# ZigBee_CC2420RTC.net
KiCad netlist of a schematic drawn in Altium Designer
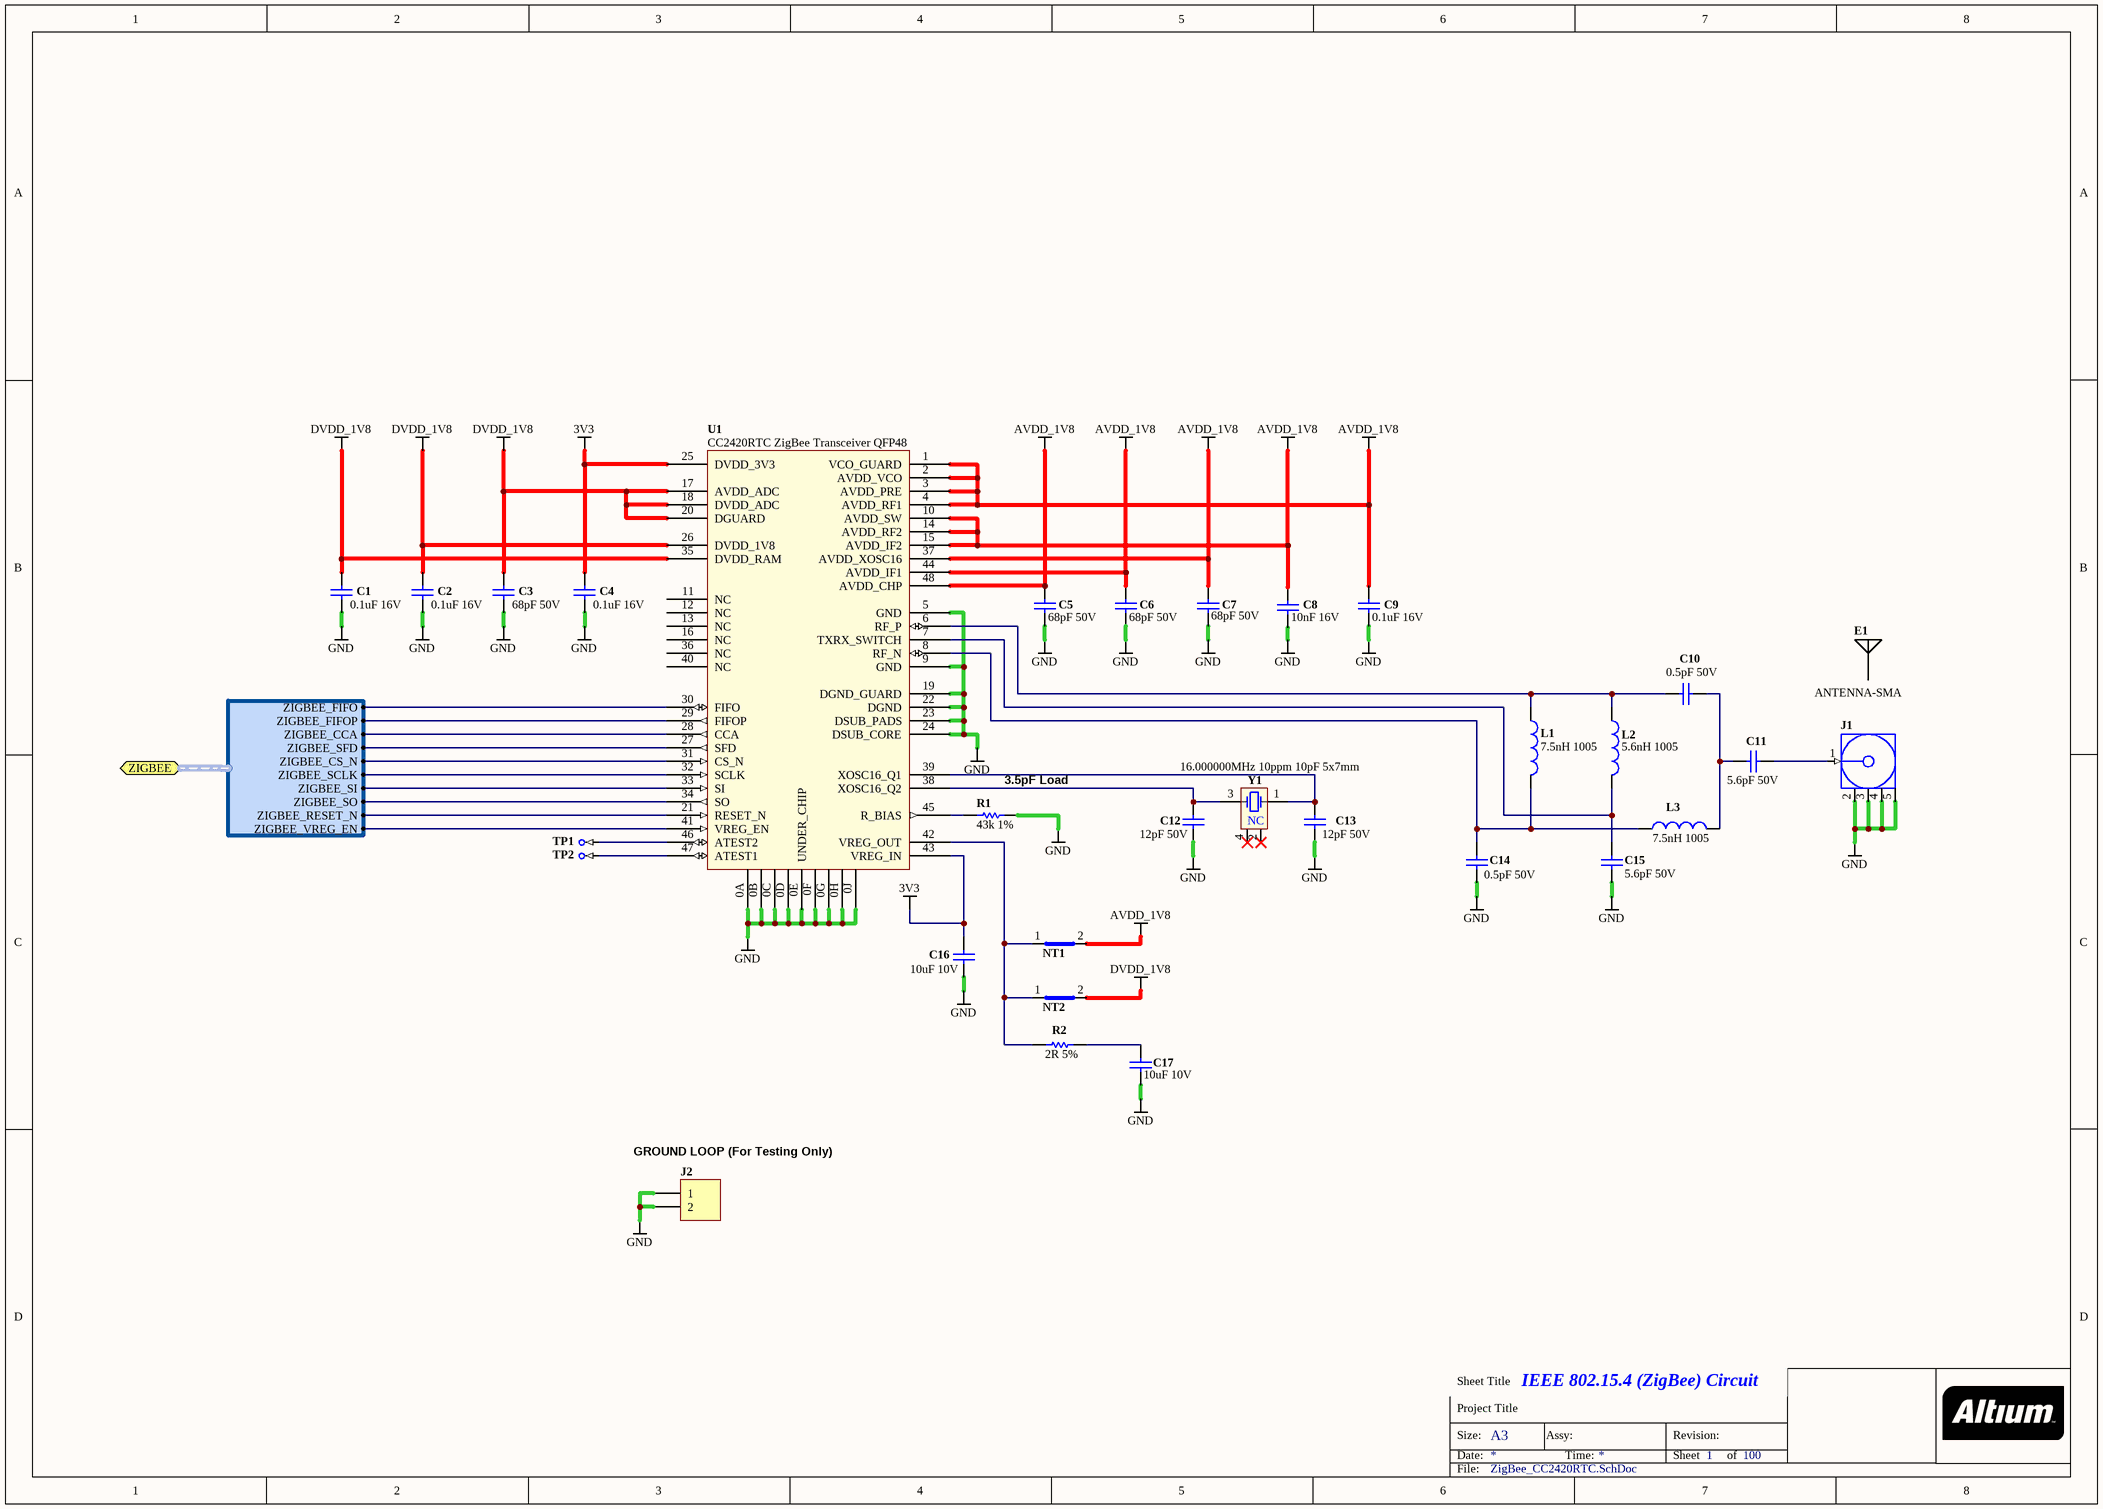
[diagram p0: ZigBee_CC2420RTC.SchDoc]

(export (version "E")
  (design (tool "Eeschema 10.0.6"))
  (components
    (comp (ref "C1")
      (value "0.1uF 16V")
      (footprint "CAPC1005-STAR")
      (description "Capacitor, Ceramic, 0.1uF 10% 16V 0402 (1005) X7R")
      (fields (field (name "TOLERANCE") "10 %"))
      (libsource (lib "AltiumDesignLibrary") (part "CAP-NP"))
    )
    (comp (ref "C2")
      (value "0.1uF 16V")
      (footprint "CAPC1005-STAR")
      (description "Capacitor, Ceramic, 0.1uF 10% 16V 0402 (1005) X7R")
      (fields (field (name "TOLERANCE") "10 %"))
      (libsource (lib "AltiumDesignLibrary") (part "CAP-NP"))
    )
    (comp (ref "C3")
      (value "68pF 50V")
      (footprint "CAPC1005-STAR")
      (description "Capacitor, Ceramic, 68pF 5% 50V 0402 (1005) COG")
      (fields (field (name "TOLERANCE") "5 %"))
      (libsource (lib "AltiumDesignLibrary") (part "CAP-NP"))
    )
    (comp (ref "C4")
      (value "0.1uF 16V")
      (footprint "CAPC1005-STAR")
      (description "Capacitor, Ceramic, 0.1uF 10% 16V 0402 (1005) X7R")
      (fields (field (name "TOLERANCE") "10 %"))
      (libsource (lib "AltiumDesignLibrary") (part "CAP-NP"))
    )
    (comp (ref "C5")
      (value "68pF 50V")
      (footprint "CAPC1005-STAR")
      (description "Capacitor, Ceramic, 68pF 5% 50V 0402 (1005) COG")
      (fields (field (name "TOLERANCE") "5 %"))
      (libsource (lib "AltiumDesignLibrary") (part "CAP-NP"))
    )
    (comp (ref "C6")
      (value "68pF 50V")
      (footprint "CAPC1005-STAR")
      (description "Capacitor, Ceramic, 68pF 5% 50V 0402 (1005) COG")
      (fields (field (name "TOLERANCE") "5 %"))
      (libsource (lib "AltiumDesignLibrary") (part "CAP-NP"))
    )
    (comp (ref "C7")
      (value "68pF 50V")
      (footprint "CAPC1005-STAR")
      (description "Capacitor, Ceramic, 68pF 5% 50V 0402 (1005) COG")
      (fields (field (name "TOLERANCE") "5 %"))
      (libsource (lib "AltiumDesignLibrary") (part "CAP-NP"))
    )
    (comp (ref "C8")
      (value "10nF 16V")
      (footprint "CAPC1005-STAR")
      (description "Capacitor, Ceramic, 10nF 10% 16V 0402 (1005) X7R")
      (fields (field (name "TOLERANCE") "10 %"))
      (libsource (lib "AltiumDesignLibrary") (part "CAP-NP"))
    )
    (comp (ref "C9")
      (value "0.1uF 16V")
      (footprint "CAPC1005-STAR")
      (description "Capacitor, Ceramic, 0.1uF 10% 16V 0402 (1005) X7R")
      (fields (field (name "TOLERANCE") "10 %"))
      (libsource (lib "AltiumDesignLibrary") (part "CAP-NP"))
    )
    (comp (ref "C10")
      (value "0.5pF 50V")
      (footprint "CAPC1005-STAR")
      (description "Capacitor, Ceramic, 0.5pF 50V 0402 (1005) COG")
      (fields (field (name "TOLERANCE") "20 %"))
      (libsource (lib "AltiumDesignLibrary") (part "CAP-NP"))
    )
    (comp (ref "C11")
      (value "5.6pF 50V")
      (footprint "CAPC1005-STAR")
      (description "Capacitor, Ceramic, 5.6pF 5% 50V 0402 (1005) COG")
      (fields (field (name "TOLERANCE") "5 %"))
      (libsource (lib "AltiumDesignLibrary") (part "CAP-NP"))
    )
    (comp (ref "C12")
      (value "12pF 50V")
      (footprint "CAPC1005-STAR")
      (description "Capacitor, Ceramic, 12pF 2% 50V 0402 (1005) COG")
      (fields (field (name "TOLERANCE") "2 %"))
      (libsource (lib "AltiumDesignLibrary") (part "CAP-NP"))
    )
    (comp (ref "C13")
      (value "12pF 50V")
      (footprint "CAPC1005-STAR")
      (description "Capacitor, Ceramic, 12pF 2% 50V 0402 (1005) COG")
      (fields (field (name "TOLERANCE") "2 %"))
      (libsource (lib "AltiumDesignLibrary") (part "CAP-NP"))
    )
    (comp (ref "C14")
      (value "0.5pF 50V")
      (footprint "CAPC1005-STAR")
      (description "Capacitor, Ceramic, 0.5pF 50V 0402 (1005) COG")
      (fields (field (name "TOLERANCE") "20 %"))
      (libsource (lib "AltiumDesignLibrary") (part "CAP-NP"))
    )
    (comp (ref "C15")
      (value "5.6pF 50V")
      (footprint "CAPC1005-STAR")
      (description "Capacitor, Ceramic, 5.6pF 5% 50V 0402 (1005) COG")
      (fields (field (name "TOLERANCE") "5 %"))
      (libsource (lib "AltiumDesignLibrary") (part "CAP-NP"))
    )
    (comp (ref "C16")
      (value "10uF 10V")
      (footprint "CAPC3216-STAR")
      (description "Capacitor, Ceramic, 10uF 10% 10V 1206 (3216) X5R")
      (fields (field (name "TOLERANCE") "10 %"))
      (libsource (lib "AltiumDesignLibrary") (part "CAP-NP"))
    )
    (comp (ref "C17")
      (value "10uF 10V")
      (footprint "CAPC3216-STAR")
      (description "Capacitor, Ceramic, 10uF 10% 10V 1206 (3216) X5R")
      (fields (field (name "TOLERANCE") "10 %"))
      (libsource (lib "AltiumDesignLibrary") (part "CAP-NP"))
    )
    (comp (ref "E1")
      (value "ANTENNA-SMA")
      (description "Antenna, 2.45GHz 1/4 Wave 50R SMA Antenna")
      (libsource (lib "AltiumDesignLibrary") (part "ANTENNA-0-PIN"))
    )
    (comp (ref "J1")
      (value "SMA 5-pin Vertical Jack 50R")
      (footprint "HDR-SMA-THD-5-PIN")
      (description "SMA RF Coaxial PCB Connector, 5-pin Through-hole, Vertical Mount Socket, 50 ohm impedance")
      (libsource (lib "AltiumDesignLibrary") (part "CON-HDR-COAXIAL-5-PIN"))
    )
    (comp (ref "J2")
      (value "1x2 HEADER MALE")
      (footprint "HDR1X2")
      (description "Header IDC, 2 x 1 Pin Vertical 2.54mm Pitch (Non-Boxed, Male)")
      (libsource (lib "AltiumDesignLibrary") (part "CON-HDR-1x2-STR"))
    )
    (comp (ref "L1")
      (value "7.5nH 1005")
      (footprint "INDC1005")
      (description "Inductor, Chip 7.5nH 300mA DCR=0.24 ohm, High Frequency 0402 (1005)")
      (libsource (lib "AltiumDesignLibrary") (part "IND"))
    )
    (comp (ref "L2")
      (value "5.6nH 1005")
      (footprint "INDC1005")
      (description "Inductor, Chip 5.6nH 300mA DCR=0.2 ohm, High Frequency 0402 (1005)")
      (libsource (lib "AltiumDesignLibrary") (part "IND"))
    )
    (comp (ref "L3")
      (value "7.5nH 1005")
      (footprint "INDC1005")
      (description "Inductor, Chip 7.5nH 300mA DCR=0.24 ohm, High Frequency 0402 (1005)")
      (libsource (lib "AltiumDesignLibrary") (part "IND"))
    )
    (comp (ref "NT1")
      (value "Net Tie SMT2")
      (footprint "NETTIE-SMT2-16X11")
      (description "Net-Tie, Surface Mount, 2 x 0.8mm x 0.4mm SMT Pads - For 0.4mm Track")
      (libsource (lib "AltiumDesignLibrary") (part "NETTIE-SMT2"))
    )
    (comp (ref "NT2")
      (value "Net Tie SMT2")
      (footprint "NETTIE-SMT2-16X11")
      (description "Net-Tie, Surface Mount, 2 x 0.8mm x 0.4mm SMT Pads - For 0.4mm Track")
      (libsource (lib "AltiumDesignLibrary") (part "NETTIE-SMT2"))
    )
    (comp (ref "R1")
      (value "43k 1%")
      (footprint "RESC1005-STAR")
      (description "Resistor, 43k 1% 0402 (1005)")
      (fields (field (name "TOLERANCE") "1 %"))
      (libsource (lib "AltiumDesignLibrary") (part "RES"))
    )
    (comp (ref "R2")
      (value "2R 5%")
      (footprint "RESC1005-STAR")
      (description "Resistopr, 2R 5% 0402 (1005)")
      (fields (field (name "TOLERANCE") "5 %"))
      (libsource (lib "AltiumDesignLibrary") (part "RES"))
    )
    (comp (ref "TP1")
      (value "TestPin")
      (footprint "TestPin")
      (description "Test Point, PCB Mount with Silkscreen Box")
      (libsource (lib "AltiumDesignLibrary") (part "TestPin"))
    )
    (comp (ref "TP2")
      (value "TestPin")
      (footprint "TestPin")
      (description "Test Point, PCB Mount with Silkscreen Box")
      (libsource (lib "AltiumDesignLibrary") (part "TestPin"))
    )
    (comp (ref "U1")
      (value "CC2420RTC ZigBee Transceiver QFP48")
      (footprint "SQFP50P700X700-48")
      (description "CC2420RTC, 2.45GHz IEEE 802.15.4 (Zigbee) RF Transceiver QFP48")
      (libsource (lib "AltiumDesignLibrary") (part "IC-CC2420RTC"))
    )
    (comp (ref "Y1")
      (value "16.000000MHz 10ppm 10pF 5x7mm")
      (footprint "XTAL-7X5")
      (description "Crystal, 16.000000MHz, 5x7mm, 10ppm 10ppm 10pF")
      (libsource (lib "AltiumDesignLibrary") (part "CRYSTAL-4PINS-1-TO-3"))
    )
  )
  (nets
    (net (code "2") (name "/ZIGBEE_CCA") (class "Default")
      (node (ref "U1") (pin "28") (pinfunction "CCA_28") (pintype "output"))
    )
    (net (code "3") (name "/ZIGBEE_CS_N") (class "Default")
      (node (ref "U1") (pin "31") (pinfunction "CS_N_31") (pintype "input"))
    )
    (net (code "4") (name "/ZIGBEE_FIFO") (class "Default")
      (node (ref "U1") (pin "30") (pinfunction "FIFO_30") (pintype "bidirectional"))
    )
    (net (code "5") (name "/ZIGBEE_FIFOP") (class "Default")
      (node (ref "U1") (pin "29") (pinfunction "FIFOP_29") (pintype "output"))
    )
    (net (code "6") (name "/ZIGBEE_RESET_N") (class "Default")
      (node (ref "U1") (pin "21") (pinfunction "RESET_N_21") (pintype "input"))
    )
    (net (code "7") (name "/ZIGBEE_SCLK") (class "Default")
      (node (ref "U1") (pin "32") (pinfunction "SCLK_32") (pintype "input"))
    )
    (net (code "8") (name "/ZIGBEE_SFD") (class "Default")
      (node (ref "U1") (pin "27") (pinfunction "SFD_27") (pintype "output"))
    )
    (net (code "9") (name "/ZIGBEE_SI") (class "Default")
      (node (ref "U1") (pin "33") (pinfunction "SI_33") (pintype "input"))
    )
    (net (code "10") (name "/ZIGBEE_SO") (class "Default")
      (node (ref "U1") (pin "34") (pinfunction "SO_34") (pintype "output"))
    )
    (net (code "11") (name "/ZIGBEE_VREG_EN") (class "Default")
      (node (ref "U1") (pin "41") (pinfunction "VREG_EN_41") (pintype "input"))
    )
    (net (code "13") (name "3V3") (class "Default")
      (node (ref "C16") (pin "1") (pinfunction "1_1") (pintype "passive"))
      (node (ref "C4") (pin "1") (pinfunction "1_1") (pintype "passive"))
      (node (ref "U1") (pin "25") (pinfunction "DVDD_3V3_25") (pintype "passive"))
      (node (ref "U1") (pin "43") (pinfunction "VREG_IN_43") (pintype "passive"))
    )
    (net (code "14") (name "AVDD_1V8") (class "Default")
      (node (ref "C5") (pin "1") (pinfunction "1_1") (pintype "passive"))
      (node (ref "C6") (pin "1") (pinfunction "1_1") (pintype "passive"))
      (node (ref "C7") (pin "1") (pinfunction "1_1") (pintype "passive"))
      (node (ref "C8") (pin "1") (pinfunction "1_1") (pintype "passive"))
      (node (ref "C9") (pin "1") (pinfunction "1_1") (pintype "passive"))
      (node (ref "NT1") (pin "2") (pinfunction "Net2_2") (pintype "passive"))
      (node (ref "U1") (pin "1") (pinfunction "VCO_GUARD_1") (pintype "passive"))
      (node (ref "U1") (pin "10") (pinfunction "AVDD_SW_10") (pintype "passive"))
      (node (ref "U1") (pin "14") (pinfunction "AVDD_RF2_14") (pintype "passive"))
      (node (ref "U1") (pin "15") (pinfunction "AVDD_IF2_15") (pintype "passive"))
      (node (ref "U1") (pin "2") (pinfunction "AVDD_VCO_2") (pintype "passive"))
      (node (ref "U1") (pin "3") (pinfunction "AVDD_PRE_3") (pintype "passive"))
      (node (ref "U1") (pin "37") (pinfunction "AVDD_XOSC16_37") (pintype "passive"))
      (node (ref "U1") (pin "4") (pinfunction "AVDD_RF1_4") (pintype "passive"))
      (node (ref "U1") (pin "44") (pinfunction "AVDD_IF1_44") (pintype "passive"))
      (node (ref "U1") (pin "48") (pinfunction "AVDD_CHP_48") (pintype "passive"))
    )
    (net (code "15") (name "DVDD_1V8") (class "Default")
      (node (ref "C1") (pin "1") (pinfunction "1_1") (pintype "passive"))
      (node (ref "C2") (pin "1") (pinfunction "1_1") (pintype "passive"))
      (node (ref "C3") (pin "1") (pinfunction "1_1") (pintype "passive"))
      (node (ref "NT2") (pin "2") (pinfunction "Net2_2") (pintype "passive"))
      (node (ref "U1") (pin "17") (pinfunction "AVDD_ADC_17") (pintype "passive"))
      (node (ref "U1") (pin "18") (pinfunction "DVDD_ADC_18") (pintype "passive"))
      (node (ref "U1") (pin "20") (pinfunction "DGUARD_20") (pintype "passive"))
      (node (ref "U1") (pin "26") (pinfunction "DVDD_1V8_26") (pintype "passive"))
      (node (ref "U1") (pin "35") (pinfunction "DVDD_RAM_35") (pintype "passive"))
    )
    (net (code "16") (name "GND") (class "Default")
      (node (ref "C1") (pin "2") (pinfunction "2_2") (pintype "passive"))
      (node (ref "C12") (pin "1") (pinfunction "1_1") (pintype "passive"))
      (node (ref "C13") (pin "1") (pinfunction "1_1") (pintype "passive"))
      (node (ref "C14") (pin "1") (pinfunction "1_1") (pintype "passive"))
      (node (ref "C15") (pin "2") (pinfunction "2_2") (pintype "passive"))
      (node (ref "C16") (pin "2") (pinfunction "2_2") (pintype "passive"))
      (node (ref "C17") (pin "2") (pinfunction "2_2") (pintype "passive"))
      (node (ref "C2") (pin "2") (pinfunction "2_2") (pintype "passive"))
      (node (ref "C3") (pin "2") (pinfunction "2_2") (pintype "passive"))
      (node (ref "C4") (pin "2") (pinfunction "2_2") (pintype "passive"))
      (node (ref "C5") (pin "2") (pinfunction "2_2") (pintype "passive"))
      (node (ref "C6") (pin "2") (pinfunction "2_2") (pintype "passive"))
      (node (ref "C7") (pin "2") (pinfunction "2_2") (pintype "passive"))
      (node (ref "C8") (pin "2") (pinfunction "2_2") (pintype "passive"))
      (node (ref "C9") (pin "2") (pinfunction "2_2") (pintype "passive"))
      (node (ref "J1") (pin "2") (pinfunction "GND_2") (pintype "passive"))
      (node (ref "J1") (pin "3") (pinfunction "GND_3") (pintype "passive"))
      (node (ref "J1") (pin "4") (pinfunction "GND_4") (pintype "passive"))
      (node (ref "J1") (pin "5") (pinfunction "GND_5") (pintype "passive"))
      (node (ref "J2") (pin "1") (pinfunction "1_1") (pintype "passive"))
      (node (ref "J2") (pin "2") (pinfunction "2_2") (pintype "passive"))
      (node (ref "R1") (pin "2") (pinfunction "2_2") (pintype "passive"))
      (node (ref "U1") (pin "0A") (pintype "passive"))
      (node (ref "U1") (pin "0B") (pintype "passive"))
      (node (ref "U1") (pin "0C") (pintype "passive"))
      (node (ref "U1") (pin "0D") (pintype "passive"))
      (node (ref "U1") (pin "0E") (pinfunction "UNDER_CHIP_0E") (pintype "passive"))
      (node (ref "U1") (pin "0F") (pintype "passive"))
      (node (ref "U1") (pin "0G") (pintype "passive"))
      (node (ref "U1") (pin "0H") (pintype "passive"))
      (node (ref "U1") (pin "0J") (pintype "passive"))
      (node (ref "U1") (pin "19") (pinfunction "DGND_GUARD_19") (pintype "passive"))
      (node (ref "U1") (pin "22") (pinfunction "DGND_22") (pintype "passive"))
      (node (ref "U1") (pin "23") (pinfunction "DSUB_PADS_23") (pintype "passive"))
      (node (ref "U1") (pin "24") (pinfunction "DSUB_CORE_24") (pintype "passive"))
      (node (ref "U1") (pin "5") (pinfunction "GND_5") (pintype "passive"))
      (node (ref "U1") (pin "9") (pinfunction "GND_9") (pintype "passive"))
    )
    (net (code "17") (name "Net-(C10-Pad2)") (class "Default")
      (node (ref "C10") (pin "2") (pinfunction "2_2") (pintype "passive"))
      (node (ref "C11") (pin "1") (pinfunction "1_1") (pintype "passive"))
      (node (ref "L3") (pin "2") (pinfunction "2_2") (pintype "passive"))
    )
    (net (code "18") (name "Net-(C17-Pad1)") (class "Default")
      (node (ref "C17") (pin "1") (pinfunction "1_1") (pintype "passive"))
      (node (ref "R2") (pin "2") (pinfunction "2_2") (pintype "passive"))
    )
    (net (code "19") (name "Net-(J1-Signal)") (class "Default")
      (node (ref "C11") (pin "2") (pinfunction "2_2") (pintype "passive"))
      (node (ref "J1") (pin "1") (pinfunction "Signal_1") (pintype "input"))
    )
    (net (code "20") (name "Net-(NT1-Net1)") (class "Default")
      (node (ref "NT1") (pin "1") (pinfunction "Net1_1") (pintype "passive"))
      (node (ref "NT2") (pin "1") (pinfunction "Net1_1") (pintype "passive"))
      (node (ref "R2") (pin "1") (pinfunction "1_1") (pintype "passive"))
      (node (ref "U1") (pin "42") (pinfunction "VREG_OUT_42") (pintype "passive"))
    )
    (net (code "21") (name "Net-(U1-ATEST1)") (class "Default")
      (node (ref "TP2") (pin "1") (pinfunction "1_1") (pintype "input"))
      (node (ref "U1") (pin "47") (pinfunction "ATEST1_47") (pintype "bidirectional"))
    )
    (net (code "22") (name "Net-(U1-ATEST2)") (class "Default")
      (node (ref "TP1") (pin "1") (pinfunction "1_1") (pintype "input"))
      (node (ref "U1") (pin "46") (pinfunction "ATEST2_46") (pintype "bidirectional"))
    )
    (net (code "23") (name "Net-(U1-RF_N)") (class "Default")
      (node (ref "C14") (pin "2") (pinfunction "2_2") (pintype "passive"))
      (node (ref "L1") (pin "2") (pinfunction "2_2") (pintype "passive"))
      (node (ref "L3") (pin "1") (pinfunction "1_1") (pintype "passive"))
      (node (ref "U1") (pin "8") (pinfunction "RF_N_8") (pintype "bidirectional"))
    )
    (net (code "24") (name "Net-(U1-RF_P)") (class "Default")
      (node (ref "C10") (pin "1") (pinfunction "1_1") (pintype "passive"))
      (node (ref "L1") (pin "1") (pinfunction "1_1") (pintype "passive"))
      (node (ref "L2") (pin "1") (pinfunction "1_1") (pintype "passive"))
      (node (ref "U1") (pin "6") (pinfunction "RF_P_6") (pintype "bidirectional"))
    )
    (net (code "25") (name "Net-(U1-R_BIAS)") (class "Default")
      (node (ref "R1") (pin "1") (pinfunction "1_1") (pintype "passive"))
      (node (ref "U1") (pin "45") (pinfunction "R_BIAS_45") (pintype "output"))
    )
    (net (code "26") (name "Net-(U1-TXRX_SWITCH)") (class "Default")
      (node (ref "C15") (pin "1") (pinfunction "1_1") (pintype "passive"))
      (node (ref "L2") (pin "2") (pinfunction "2_2") (pintype "passive"))
      (node (ref "U1") (pin "7") (pinfunction "TXRX_SWITCH_7") (pintype "passive"))
    )
    (net (code "27") (name "Net-(U1-XOSC16_Q1)") (class "Default")
      (node (ref "C13") (pin "2") (pinfunction "2_2") (pintype "passive"))
      (node (ref "U1") (pin "39") (pinfunction "XOSC16_Q1_39") (pintype "passive"))
      (node (ref "Y1") (pin "1") (pinfunction "X1_1") (pintype "passive"))
    )
    (net (code "28") (name "Net-(U1-XOSC16_Q2)") (class "Default")
      (node (ref "C12") (pin "2") (pinfunction "2_2") (pintype "passive"))
      (node (ref "U1") (pin "38") (pinfunction "XOSC16_Q2_38") (pintype "passive"))
      (node (ref "Y1") (pin "3") (pinfunction "X2_3") (pintype "passive"))
    )
    (net (code "29") (name "unconnected-(U1-NC-Pad11)") (class "Default")
      (node (ref "U1") (pin "11") (pinfunction "NC_11") (pintype "passive"))
    )
    (net (code "30") (name "unconnected-(U1-NC-Pad12)") (class "Default")
      (node (ref "U1") (pin "12") (pinfunction "NC_12") (pintype "passive"))
    )
    (net (code "31") (name "unconnected-(U1-NC-Pad13)") (class "Default")
      (node (ref "U1") (pin "13") (pinfunction "NC_13") (pintype "passive"))
    )
    (net (code "32") (name "unconnected-(U1-NC-Pad16)") (class "Default")
      (node (ref "U1") (pin "16") (pinfunction "NC_16") (pintype "passive"))
    )
    (net (code "33") (name "unconnected-(U1-NC-Pad36)") (class "Default")
      (node (ref "U1") (pin "36") (pinfunction "NC_36") (pintype "passive"))
    )
    (net (code "34") (name "unconnected-(U1-NC-Pad40)") (class "Default")
      (node (ref "U1") (pin "40") (pinfunction "NC_40") (pintype "passive"))
    )
    (net (code "35") (name "unconnected-(Y1-NC-Pad2)") (class "Default")
      (node (ref "Y1") (pin "2") (pinfunction "NC_2") (pintype "passive+no_connect"))
    )
    (net (code "36") (name "unconnected-(Y1-NC-Pad4)") (class "Default")
      (node (ref "Y1") (pin "4") (pinfunction "NC_4") (pintype "passive+no_connect"))
    )
  )
)
